# 2022-11-04_ESP32-CX_Riser.net
KiCad netlist of a schematic drawn in EasyEDA
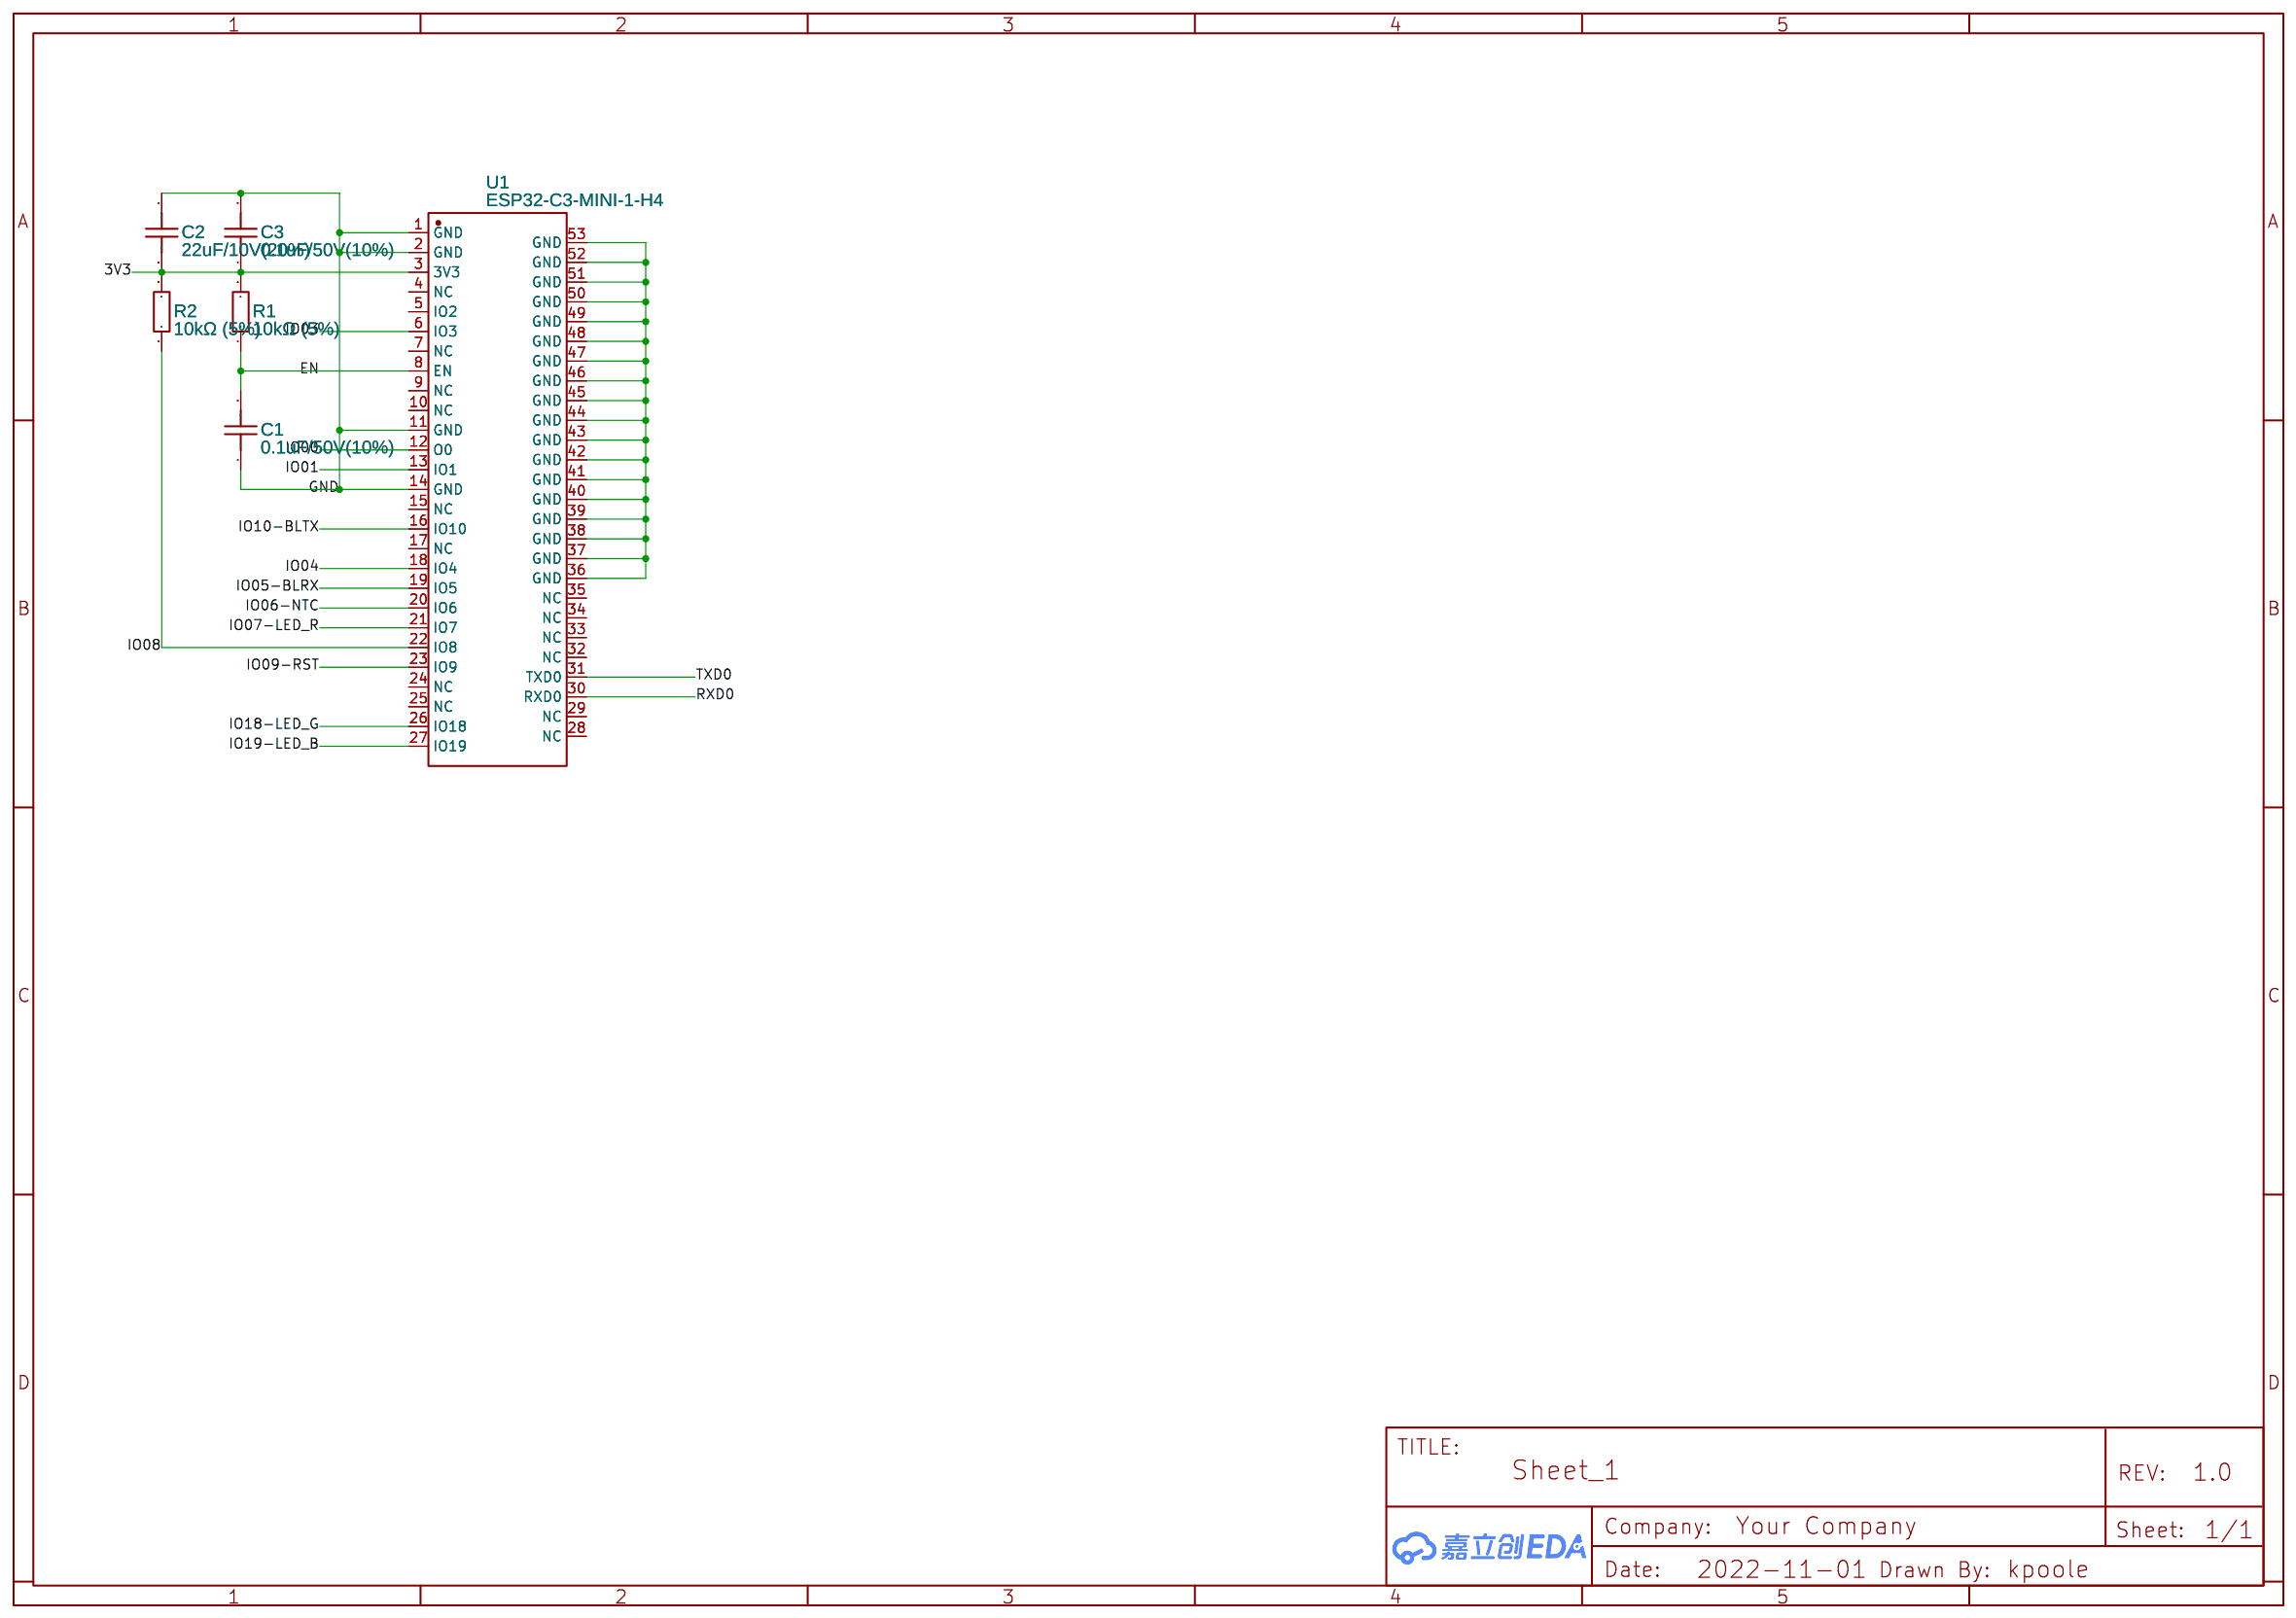
[diagram p0: schematic sheet]

(export (version "E")
  (design (tool "Eeschema 10.0.6"))
  (components
    (comp (ref "C1")
      (value "0.1uF/50V(10%)")
      (fields
        (field (name "BOM_Manufacturer Part") "0603BB104K500NGT")
        (field (name "BOM_Supplier Part") "C2168571")
      )
      (libsource (lib "") (part "0603BB104K500NGT"))
    )
    (comp (ref "C2")
      (value "22uF/10V(20%)")
      (fields
        (field (name "BOM_Manufacturer Part") "CL10A226MP8NUNE")
        (field (name "BOM_Supplier Part") "C86295")
      )
      (libsource (lib "") (part "CL10A226MP8NUNE"))
    )
    (comp (ref "C3")
      (value "0.1uF/50V(10%)")
      (fields
        (field (name "BOM_Manufacturer Part") "CAP-SMD-0603-10uF-50V-10%")
        (field (name "BOM_Supplier Part") "C9900006127")
      )
      (libsource (lib "") (part "CAP-SMD-0603-10UF-50V-10%"))
    )
    (comp (ref "R1")
      (value "10kΩ (5%)")
      (fields
        (field (name "BOM_Manufacturer Part") "RK73B2ATTD103J")
        (field (name "BOM_Supplier Part") "C159912")
      )
      (libsource (lib "") (part "RK73B2ATTD103J"))
    )
    (comp (ref "R2")
      (value "10kΩ (5%)")
      (fields
        (field (name "BOM_Manufacturer Part") "RK73B2ATTD103J")
        (field (name "BOM_Supplier Part") "C159912")
      )
      (libsource (lib "") (part "RK73B2ATTD103J"))
    )
    (comp (ref "U1")
      (value "ESP32-C3-MINI-1-H4")
      (fields (field (name "BOM_Supplier Part") "C2935306"))
      (libsource (lib "") (part "ESP32-C3-MINI-1-H4"))
    )
  )
  (nets
    (net (code "1") (name "/3V3") (class "Default")
      (node (ref "C2") (pin "2") (pinfunction "2_2") (pintype "unspecified"))
      (node (ref "C3") (pin "1") (pinfunction "1_1") (pintype "unspecified"))
      (node (ref "R1") (pin "2") (pinfunction "2_2") (pintype "unspecified"))
      (node (ref "R2") (pin "2") (pinfunction "2_2") (pintype "unspecified"))
      (node (ref "U1") (pin "3") (pinfunction "3V3_3") (pintype "unspecified"))
    )
    (net (code "2") (name "/EN") (class "Default")
      (node (ref "C1") (pin "2") (pinfunction "2_2") (pintype "unspecified"))
      (node (ref "R1") (pin "1") (pinfunction "1_1") (pintype "unspecified"))
      (node (ref "U1") (pin "8") (pinfunction "EN_8") (pintype "unspecified"))
    )
    (net (code "3") (name "/GND") (class "Default")
      (node (ref "C1") (pin "1") (pinfunction "1_1") (pintype "unspecified"))
      (node (ref "C2") (pin "1") (pinfunction "1_1") (pintype "unspecified"))
      (node (ref "C3") (pin "2") (pinfunction "2_2") (pintype "unspecified"))
      (node (ref "U1") (pin "1") (pinfunction "GND_1") (pintype "unspecified"))
      (node (ref "U1") (pin "11") (pinfunction "GND_11") (pintype "unspecified"))
      (node (ref "U1") (pin "14") (pinfunction "GND_14") (pintype "unspecified"))
      (node (ref "U1") (pin "2") (pinfunction "GND_2") (pintype "unspecified"))
    )
    (net (code "4") (name "/IO00") (class "Default")
      (node (ref "U1") (pin "12") (pinfunction "O0_12") (pintype "unspecified"))
    )
    (net (code "5") (name "/IO01") (class "Default")
      (node (ref "U1") (pin "13") (pinfunction "IO1_13") (pintype "unspecified"))
    )
    (net (code "6") (name "/IO03") (class "Default")
      (node (ref "U1") (pin "6") (pinfunction "IO3_6") (pintype "unspecified"))
    )
    (net (code "7") (name "/IO04") (class "Default")
      (node (ref "U1") (pin "18") (pinfunction "IO4_18") (pintype "unspecified"))
    )
    (net (code "8") (name "/IO05-BLRX") (class "Default")
      (node (ref "U1") (pin "19") (pinfunction "IO5_19") (pintype "unspecified"))
    )
    (net (code "9") (name "/IO06-NTC") (class "Default")
      (node (ref "U1") (pin "20") (pinfunction "IO6_20") (pintype "unspecified"))
    )
    (net (code "10") (name "/IO07-LED_R") (class "Default")
      (node (ref "U1") (pin "21") (pinfunction "IO7_21") (pintype "unspecified"))
    )
    (net (code "11") (name "/IO08") (class "Default")
      (node (ref "R2") (pin "1") (pinfunction "1_1") (pintype "unspecified"))
      (node (ref "U1") (pin "22") (pinfunction "IO8_22") (pintype "unspecified"))
    )
    (net (code "12") (name "/IO09-RST") (class "Default")
      (node (ref "U1") (pin "23") (pinfunction "IO9_23") (pintype "unspecified"))
    )
    (net (code "13") (name "/IO10-BLTX") (class "Default")
      (node (ref "U1") (pin "16") (pinfunction "IO10_16") (pintype "unspecified"))
    )
    (net (code "14") (name "/IO18-LED_G") (class "Default")
      (node (ref "U1") (pin "26") (pinfunction "IO18_26") (pintype "unspecified"))
    )
    (net (code "15") (name "/IO19-LED_B") (class "Default")
      (node (ref "U1") (pin "27") (pinfunction "IO19_27") (pintype "unspecified"))
    )
    (net (code "16") (name "/RXD0") (class "Default")
      (node (ref "U1") (pin "30") (pinfunction "RXD0_30") (pintype "unspecified"))
    )
    (net (code "17") (name "/TXD0") (class "Default")
      (node (ref "U1") (pin "31") (pinfunction "TXD0_31") (pintype "unspecified"))
    )
    (net (code "18") (name "Net-(U1-GND-Pad36)") (class "Default")
      (node (ref "U1") (pin "36") (pinfunction "GND_36") (pintype "unspecified"))
      (node (ref "U1") (pin "37") (pinfunction "GND_37") (pintype "unspecified"))
      (node (ref "U1") (pin "38") (pinfunction "GND_38") (pintype "unspecified"))
      (node (ref "U1") (pin "39") (pinfunction "GND_39") (pintype "unspecified"))
      (node (ref "U1") (pin "40") (pinfunction "GND_40") (pintype "unspecified"))
      (node (ref "U1") (pin "41") (pinfunction "GND_41") (pintype "unspecified"))
      (node (ref "U1") (pin "42") (pinfunction "GND_42") (pintype "unspecified"))
      (node (ref "U1") (pin "43") (pinfunction "GND_43") (pintype "unspecified"))
      (node (ref "U1") (pin "44") (pinfunction "GND_44") (pintype "unspecified"))
      (node (ref "U1") (pin "45") (pinfunction "GND_45") (pintype "unspecified"))
      (node (ref "U1") (pin "46") (pinfunction "GND_46") (pintype "unspecified"))
      (node (ref "U1") (pin "47") (pinfunction "GND_47") (pintype "unspecified"))
      (node (ref "U1") (pin "48") (pinfunction "GND_48") (pintype "unspecified"))
      (node (ref "U1") (pin "49") (pinfunction "GND_49") (pintype "unspecified"))
      (node (ref "U1") (pin "50") (pinfunction "GND_50") (pintype "unspecified"))
      (node (ref "U1") (pin "51") (pinfunction "GND_51") (pintype "unspecified"))
      (node (ref "U1") (pin "52") (pinfunction "GND_52") (pintype "unspecified"))
      (node (ref "U1") (pin "53") (pinfunction "GND_53") (pintype "unspecified"))
    )
    (net (code "19") (name "unconnected-(U1-IO2-Pad5)") (class "Default")
      (node (ref "U1") (pin "5") (pinfunction "IO2_5") (pintype "unspecified"))
    )
    (net (code "20") (name "unconnected-(U1-NC-Pad4)") (class "Default")
      (node (ref "U1") (pin "4") (pinfunction "NC_4") (pintype "unspecified"))
    )
    (net (code "21") (name "unconnected-(U1-NC-Pad7)") (class "Default")
      (node (ref "U1") (pin "7") (pinfunction "NC_7") (pintype "unspecified"))
    )
    (net (code "22") (name "unconnected-(U1-NC-Pad9)") (class "Default")
      (node (ref "U1") (pin "9") (pinfunction "NC_9") (pintype "unspecified"))
    )
    (net (code "23") (name "unconnected-(U1-NC-Pad10)") (class "Default")
      (node (ref "U1") (pin "10") (pinfunction "NC_10") (pintype "unspecified"))
    )
    (net (code "24") (name "unconnected-(U1-NC-Pad15)") (class "Default")
      (node (ref "U1") (pin "15") (pinfunction "NC_15") (pintype "unspecified"))
    )
    (net (code "25") (name "unconnected-(U1-NC-Pad17)") (class "Default")
      (node (ref "U1") (pin "17") (pinfunction "NC_17") (pintype "unspecified"))
    )
    (net (code "26") (name "unconnected-(U1-NC-Pad24)") (class "Default")
      (node (ref "U1") (pin "24") (pinfunction "NC_24") (pintype "unspecified"))
    )
    (net (code "27") (name "unconnected-(U1-NC-Pad25)") (class "Default")
      (node (ref "U1") (pin "25") (pinfunction "NC_25") (pintype "unspecified"))
    )
    (net (code "28") (name "unconnected-(U1-NC-Pad28)") (class "Default")
      (node (ref "U1") (pin "28") (pinfunction "NC_28") (pintype "unspecified"))
    )
    (net (code "29") (name "unconnected-(U1-NC-Pad29)") (class "Default")
      (node (ref "U1") (pin "29") (pinfunction "NC_29") (pintype "unspecified"))
    )
    (net (code "30") (name "unconnected-(U1-NC-Pad32)") (class "Default")
      (node (ref "U1") (pin "32") (pinfunction "NC_32") (pintype "unspecified"))
    )
    (net (code "31") (name "unconnected-(U1-NC-Pad33)") (class "Default")
      (node (ref "U1") (pin "33") (pinfunction "NC_33") (pintype "unspecified"))
    )
    (net (code "32") (name "unconnected-(U1-NC-Pad34)") (class "Default")
      (node (ref "U1") (pin "34") (pinfunction "NC_34") (pintype "unspecified"))
    )
    (net (code "33") (name "unconnected-(U1-NC-Pad35)") (class "Default")
      (node (ref "U1") (pin "35") (pinfunction "NC_35") (pintype "unspecified"))
    )
  )
)
